# QTR.net
KiCad netlist of a schematic drawn in Altium Designer
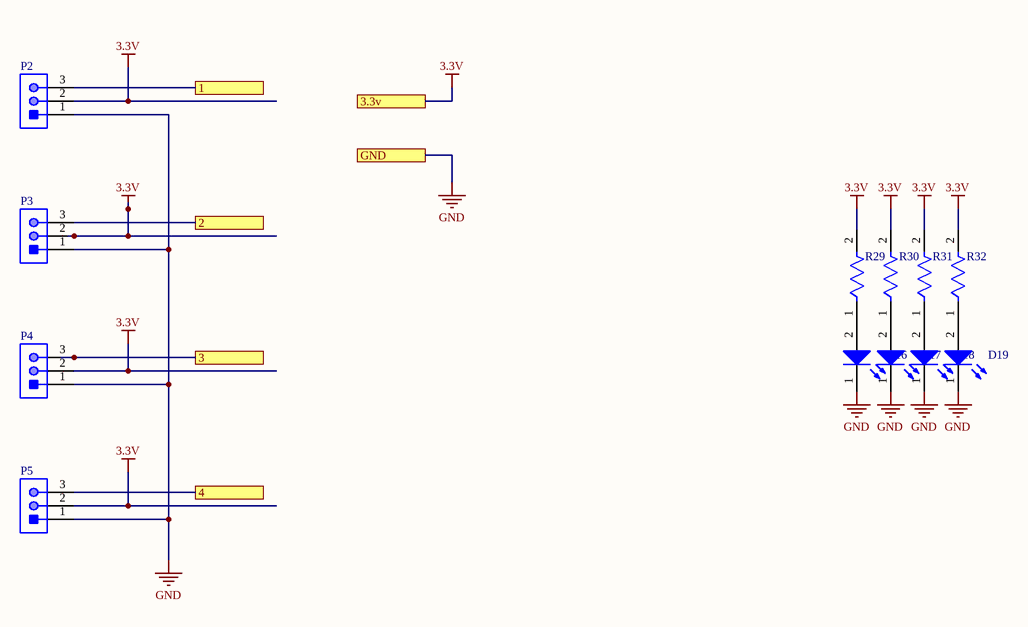
[diagram p0: QTR.SchDoc]

(export (version "E")
  (design (tool "Eeschema 10.0.6"))
  (components
    (comp (ref "D16")
      (value "150080BS75000")
      (footprint "WL-SMCW_0805_150080xx75000")
      (libsource (lib "Altium Content Vault") (part "LED_Blue_2A-1K"))
    )
    (comp (ref "D17")
      (value "150080BS75000")
      (footprint "WL-SMCW_0805_150080xx75000")
      (libsource (lib "Altium Content Vault") (part "LED_Blue_2A-1K"))
    )
    (comp (ref "D18")
      (value "150080BS75000")
      (footprint "WL-SMCW_0805_150080xx75000")
      (libsource (lib "Altium Content Vault") (part "LED_Blue_2A-1K"))
    )
    (comp (ref "D19")
      (value "150080BS75000")
      (footprint "WL-SMCW_0805_150080xx75000")
      (libsource (lib "Altium Content Vault") (part "LED_Blue_2A-1K"))
    )
    (comp (ref "P2")
      (value "B3B-PH-K-S(LF)(SN)")
      (footprint "JST-B3B-PH-K-S-3_V")
      (fields (field (name "MANUFACTURER") "JST"))
      (libsource (lib "Altium Content Vault") (part "CN-1P-M-R3"))
    )
    (comp (ref "P3")
      (value "B3B-PH-K-S(LF)(SN)")
      (footprint "JST-B3B-PH-K-S-3_V")
      (fields (field (name "MANUFACTURER") "JST"))
      (libsource (lib "Altium Content Vault") (part "CN-1P-M-R3"))
    )
    (comp (ref "P4")
      (value "B3B-PH-K-S(LF)(SN)")
      (footprint "JST-B3B-PH-K-S-3_V")
      (fields (field (name "MANUFACTURER") "JST"))
      (libsource (lib "Altium Content Vault") (part "CN-1P-M-R3"))
    )
    (comp (ref "P5")
      (value "B3B-PH-K-S(LF)(SN)")
      (footprint "JST-B3B-PH-K-S-3_V")
      (fields (field (name "MANUFACTURER") "JST"))
      (libsource (lib "Altium Content Vault") (part "CN-1P-M-R3"))
    )
    (comp (ref "R29")
      (value "ERJ-6ENF1500V")
      (footprint "FP-ERJ6EN-IPC_A")
      (fields (field (name "TOLERANCE") "1%"))
      (libsource (lib "Altium Content Vault") (part "1029c3af85768c4190bb7ad29bc67b5"))
    )
    (comp (ref "R30")
      (value "ERJ-6ENF1500V")
      (footprint "FP-ERJ6EN-IPC_A")
      (fields (field (name "TOLERANCE") "1%"))
      (libsource (lib "Altium Content Vault") (part "1029c3af85768c4190bb7ad29bc67b5"))
    )
    (comp (ref "R31")
      (value "ERJ-6ENF1500V")
      (footprint "FP-ERJ6EN-IPC_A")
      (fields (field (name "TOLERANCE") "1%"))
      (libsource (lib "Altium Content Vault") (part "1029c3af85768c4190bb7ad29bc67b5"))
    )
    (comp (ref "R32")
      (value "ERJ-6ENF1500V")
      (footprint "FP-ERJ6EN-IPC_A")
      (fields (field (name "TOLERANCE") "1%"))
      (libsource (lib "Altium Content Vault") (part "1029c3af85768c4190bb7ad29bc67b5"))
    )
  )
  (nets
    (net (code "1") (name "/1") (class "Default")
      (node (ref "P2") (pin "3") (pinfunction "3_3") (pintype "passive"))
    )
    (net (code "2") (name "/2") (class "Default")
      (node (ref "P3") (pin "3") (pinfunction "3_3") (pintype "passive"))
    )
    (net (code "3") (name "/3") (class "Default")
      (node (ref "P4") (pin "3") (pinfunction "3_3") (pintype "passive"))
    )
    (net (code "4") (name "/4") (class "Default")
      (node (ref "P5") (pin "3") (pinfunction "3_3") (pintype "passive"))
    )
    (net (code "5") (name "3.3V") (class "Default")
      (node (ref "P2") (pin "2") (pinfunction "2_2") (pintype "passive"))
      (node (ref "P3") (pin "2") (pinfunction "2_2") (pintype "passive"))
      (node (ref "P4") (pin "2") (pinfunction "2_2") (pintype "passive"))
      (node (ref "P5") (pin "2") (pinfunction "2_2") (pintype "passive"))
      (node (ref "R29") (pin "2") (pinfunction "2_2") (pintype "passive"))
      (node (ref "R30") (pin "2") (pinfunction "2_2") (pintype "passive"))
      (node (ref "R31") (pin "2") (pinfunction "2_2") (pintype "passive"))
      (node (ref "R32") (pin "2") (pinfunction "2_2") (pintype "passive"))
    )
    (net (code "6") (name "GND") (class "Default")
      (node (ref "D16") (pin "1") (pinfunction "K_1") (pintype "passive"))
      (node (ref "D17") (pin "1") (pinfunction "K_1") (pintype "passive"))
      (node (ref "D18") (pin "1") (pinfunction "K_1") (pintype "passive"))
      (node (ref "D19") (pin "1") (pinfunction "K_1") (pintype "passive"))
      (node (ref "P2") (pin "1") (pinfunction "1_1") (pintype "passive"))
      (node (ref "P3") (pin "1") (pinfunction "1_1") (pintype "passive"))
      (node (ref "P4") (pin "1") (pinfunction "1_1") (pintype "passive"))
      (node (ref "P5") (pin "1") (pinfunction "1_1") (pintype "passive"))
    )
    (net (code "7") (name "Net-(D16-A)") (class "Default")
      (node (ref "D16") (pin "2") (pinfunction "A_2") (pintype "passive"))
      (node (ref "R29") (pin "1") (pinfunction "1_1") (pintype "passive"))
    )
    (net (code "8") (name "Net-(D17-A)") (class "Default")
      (node (ref "D17") (pin "2") (pinfunction "A_2") (pintype "passive"))
      (node (ref "R30") (pin "1") (pinfunction "1_1") (pintype "passive"))
    )
    (net (code "9") (name "Net-(D18-A)") (class "Default")
      (node (ref "D18") (pin "2") (pinfunction "A_2") (pintype "passive"))
      (node (ref "R31") (pin "1") (pinfunction "1_1") (pintype "passive"))
    )
    (net (code "10") (name "Net-(D19-A)") (class "Default")
      (node (ref "D19") (pin "2") (pinfunction "A_2") (pintype "passive"))
      (node (ref "R32") (pin "1") (pinfunction "1_1") (pintype "passive"))
    )
  )
)
